# Regulators3.net
KiCad netlist of a schematic drawn in Altium Designer
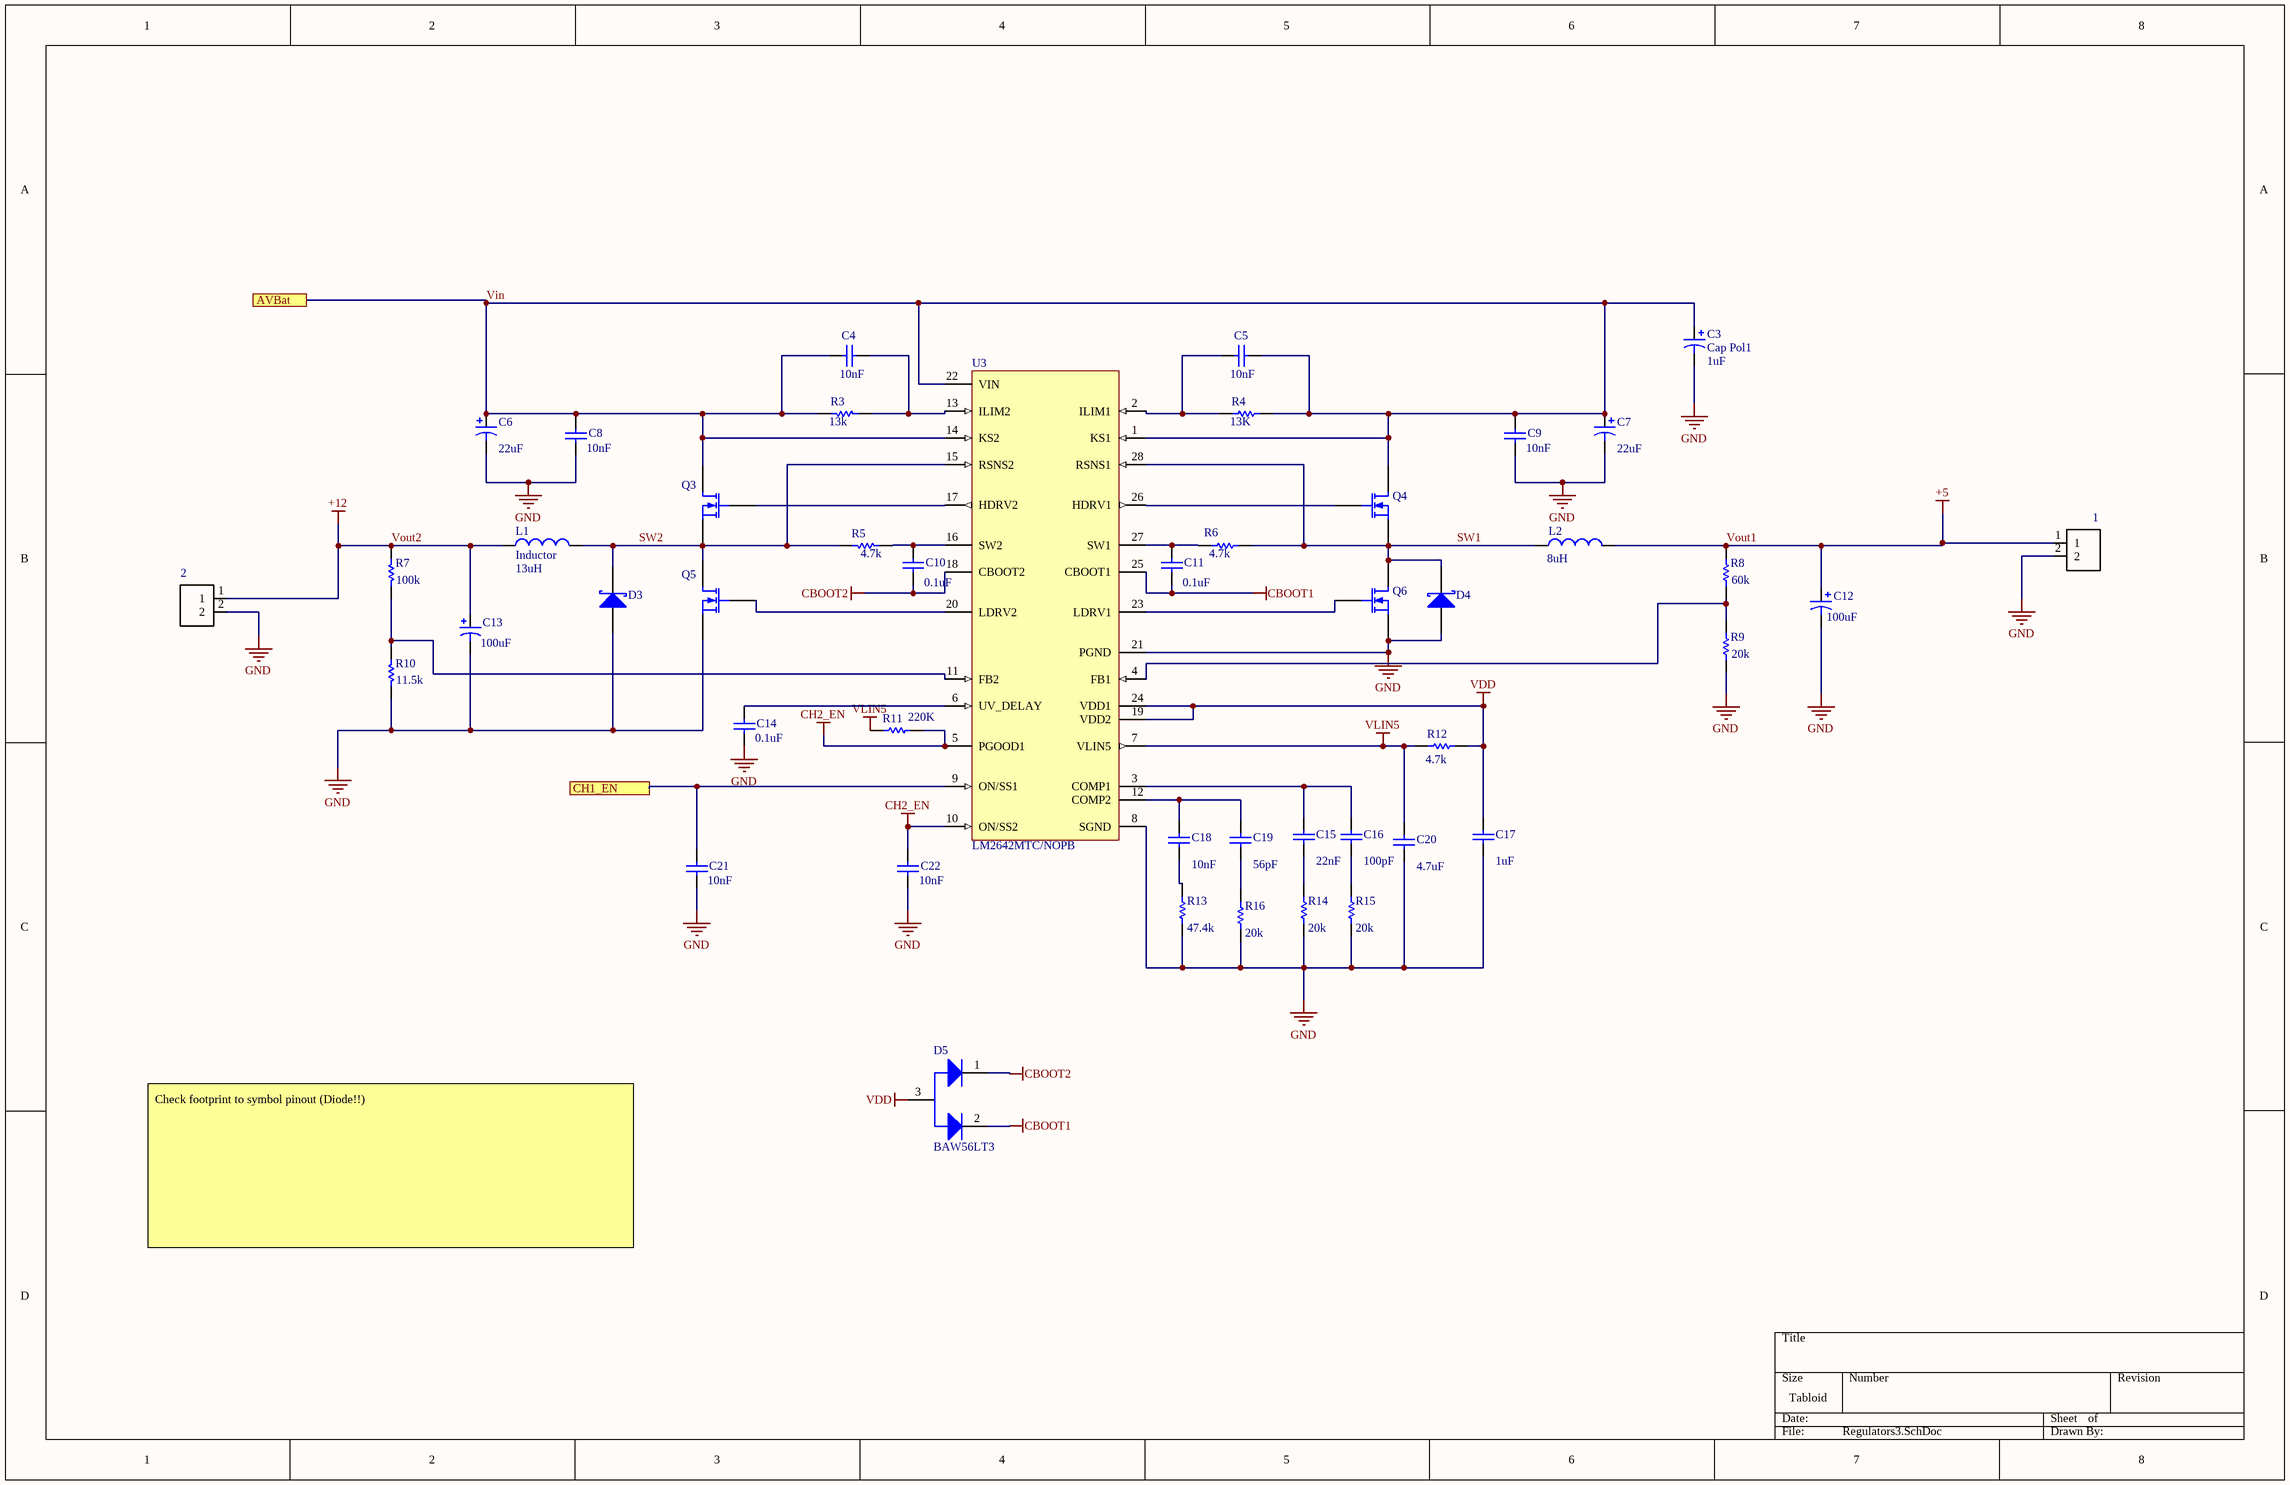
[diagram p0: Regulators3.SchDoc]

(export (version "E")
  (design (tool "Eeschema 10.0.6"))
  (components
    (comp (ref "1")
      (value "282836-2")
      (footprint "*CONN_282836-2")
      (description "Connector, Terminal Block; Wire Receptacle; 2 Pos.; 16-30 AWG; 0.197 in. CL; Sid")
      (fields (field (name "DIGI-KEY_PART_NUMBER") "A98076-ND") (field (name "MF") "TE Connectivity"))
      (libsource (lib "TerminalBlockx2") (part "282836-2"))
    )
    (comp (ref "2")
      (value "282836-2")
      (footprint "*CONN_282836-2")
      (description "Connector, Terminal Block; Wire Receptacle; 2 Pos.; 16-30 AWG; 0.197 in. CL; Sid")
      (fields (field (name "DIGI-KEY_PART_NUMBER") "A98076-ND") (field (name "MF") "TE Connectivity"))
      (libsource (lib "TerminalBlockx2") (part "282836-2"))
    )
    (comp (ref "C3")
      (value "Cap Pol1")
      (footprint "1u50VcapE")
      (description "Polarized Capacitor (Radial)")
      (fields (field (name "ALTIUM_VALUE") "1uF") (field (name "PUBLISHER") "Altium Limited"))
      (libsource (lib "Miscellaneous Devices") (part "Cap Pol1"))
    )
    (comp (ref "C4")
      (value "10nF")
      (footprint "1608[0603]")
      (description "Capacitor")
      (fields (field (name "Comment") "Cap") (field (name "PUBLISHER") "Altium Limited"))
      (libsource (lib "Miscellaneous Devices") (part "Cap"))
    )
    (comp (ref "C5")
      (value "10nF")
      (footprint "1608[0603]")
      (description "Capacitor")
      (fields (field (name "Comment") "Cap") (field (name "PUBLISHER") "Altium Limited"))
      (libsource (lib "Miscellaneous Devices") (part "Cap"))
    )
    (comp (ref "C6")
      (value "22uF")
      (footprint "22u16VcapE")
      (description "Polarized Capacitor (Radial)")
      (fields (field (name "Comment") "Cap Pol1") (field (name "PUBLISHER") "Altium Limited"))
      (libsource (lib "") (part "Cap Pol1_1"))
    )
    (comp (ref "C7")
      (value "22uF")
      (footprint "22u16VcapE")
      (description "Polarized Capacitor (Radial)")
      (fields (field (name "Comment") "Cap Pol1") (field (name "PUBLISHER") "Altium Limited"))
      (libsource (lib "Miscellaneous Devices") (part "Cap Pol1"))
    )
    (comp (ref "C8")
      (value "10nF")
      (footprint "1608[0603]")
      (description "Capacitor")
      (fields (field (name "Comment") "Cap") (field (name "PUBLISHER") "Altium Limited"))
      (libsource (lib "Miscellaneous Devices") (part "Cap"))
    )
    (comp (ref "C9")
      (value "10nF")
      (footprint "1608[0603]")
      (description "Capacitor")
      (fields (field (name "Comment") "Cap") (field (name "PUBLISHER") "Altium Limited"))
      (libsource (lib "Miscellaneous Devices") (part "Cap"))
    )
    (comp (ref "C10")
      (value "0.1uF")
      (footprint "1608[0603]")
      (description "Capacitor")
      (fields (field (name "Comment") "Cap") (field (name "PUBLISHER") "Altium Limited"))
      (libsource (lib "Miscellaneous Devices") (part "Cap"))
    )
    (comp (ref "C11")
      (value "0.1uF")
      (footprint "1608[0603]")
      (description "Capacitor")
      (fields (field (name "Comment") "Cap") (field (name "PUBLISHER") "Altium Limited"))
      (libsource (lib "Miscellaneous Devices") (part "Cap"))
    )
    (comp (ref "C12")
      (value "100uF")
      (footprint "*CAPAE660X800N")
      (description "Polarized Capacitor (Radial)")
      (fields (field (name "Comment") "Cap Pol1") (field (name "PUBLISHER") "Altium Limited"))
      (libsource (lib "Miscellaneous Devices") (part "Cap Pol1"))
    )
    (comp (ref "C13")
      (value "100uF")
      (footprint "*CAPAE660X800N")
      (description "Polarized Capacitor (Radial)")
      (fields (field (name "Comment") "Cap Pol1") (field (name "PUBLISHER") "Altium Limited"))
      (libsource (lib "") (part "Cap Pol1_1"))
    )
    (comp (ref "C14")
      (value "0.1uF")
      (footprint "1608[0603]")
      (description "Capacitor")
      (fields (field (name "Comment") "Cap") (field (name "PUBLISHER") "Altium Limited"))
      (libsource (lib "Miscellaneous Devices") (part "Cap"))
    )
    (comp (ref "C15")
      (value "22nF")
      (footprint "1608[0603]")
      (description "Capacitor")
      (fields (field (name "Comment") "Cap") (field (name "PUBLISHER") "Altium Limited"))
      (libsource (lib "Miscellaneous Devices") (part "Cap"))
    )
    (comp (ref "C16")
      (value "100pF")
      (footprint "1608[0603]")
      (description "Capacitor")
      (fields (field (name "Comment") "Cap") (field (name "PUBLISHER") "Altium Limited"))
      (libsource (lib "Miscellaneous Devices") (part "Cap"))
    )
    (comp (ref "C17")
      (value "1uF")
      (footprint "1608[0603]")
      (description "Capacitor")
      (fields (field (name "Comment") "Cap") (field (name "PUBLISHER") "Altium Limited"))
      (libsource (lib "Miscellaneous Devices") (part "Cap"))
    )
    (comp (ref "C18")
      (value "10nF")
      (footprint "1608[0603]")
      (description "Capacitor")
      (fields (field (name "Comment") "Cap") (field (name "PUBLISHER") "Altium Limited"))
      (libsource (lib "Miscellaneous Devices") (part "Cap"))
    )
    (comp (ref "C19")
      (value "56pF")
      (footprint "1608[0603]")
      (description "Capacitor")
      (fields (field (name "Comment") "Cap") (field (name "PUBLISHER") "Altium Limited"))
      (libsource (lib "Miscellaneous Devices") (part "Cap"))
    )
    (comp (ref "C20")
      (value "4.7uF")
      (footprint "1608[0603]")
      (description "Capacitor")
      (fields (field (name "Comment") "Cap") (field (name "PUBLISHER") "Altium Limited"))
      (libsource (lib "Miscellaneous Devices") (part "Cap"))
    )
    (comp (ref "C21")
      (value "10nF")
      (footprint "1608[0603]")
      (description "Capacitor")
      (fields (field (name "Comment") "Cap") (field (name "PUBLISHER") "Altium Limited"))
      (libsource (lib "Miscellaneous Devices") (part "Cap"))
    )
    (comp (ref "C22")
      (value "10nF")
      (footprint "1608[0603]")
      (description "Capacitor")
      (fields (field (name "Comment") "Cap") (field (name "PUBLISHER") "Altium Limited"))
      (libsource (lib "Miscellaneous Devices") (part "Cap"))
    )
    (comp (ref "D3")
      (value "Diode MBRS140t3")
      (footprint "*DIOM5227X270N_S1M(Primary)")
      (description "Schottky Rectifier")
      (fields (field (name "PUBLISHER") "Altium Limited"))
      (libsource (lib "Miscellaneous Devices") (part "Diode 18TQ045"))
    )
    (comp (ref "D4")
      (value "Diode MBRS140t3")
      (footprint "*DIOM5227X270N_S1M(Primary)")
      (description "Schottky Rectifier")
      (fields (field (name "PUBLISHER") "Altium Limited"))
      (libsource (lib "Miscellaneous Devices") (part "Diode 18TQ045"))
    )
    (comp (ref "D5")
      (value "BAW56LT3")
      (footprint "ONSC-SOT-23-3-318-08_V")
      (description "Dual Switching Diodes, Common Anode, 3-Pin SOT-23, Tape and Reel")
      (fields (field (name "MANUFACTURER") "On Semiconductor"))
      (libsource (lib "ON Semi Small Signal Switching Diodes") (part "BAW56LT3"))
    )
    (comp (ref "L1")
      (value "Inductor")
      (footprint "Inductor")
      (fields (field (name "ALTIUM_VALUE") "13uH") (field (name "PUBLISHER") "Altium Limited"))
      (libsource (lib "Miscellaneous Devices") (part "Inductor"))
    )
    (comp (ref "L2")
      (value "8uH")
      (footprint "Inductor")
      (description "Inductor")
      (fields (field (name "PUBLISHER") "Altium Limited"))
      (libsource (lib "Miscellaneous Devices") (part "Inductor"))
    )
    (comp (ref "Q3")
      (value "MOSFET-N")
      (footprint "SO8_L")
      (description "N-Channel MOSFET")
      (fields (field (name "PUBLISHER") "Altium Limited"))
      (libsource (lib "Miscellaneous Devices") (part "MOSFET-N"))
    )
    (comp (ref "Q4")
      (value "MOSFET-N")
      (footprint "SO8_L")
      (description "N-Channel MOSFET")
      (fields (field (name "PUBLISHER") "Altium Limited"))
      (libsource (lib "Miscellaneous Devices") (part "MOSFET-N"))
    )
    (comp (ref "Q5")
      (value "MOSFET-N")
      (footprint "SO8_L")
      (description "N-Channel MOSFET")
      (fields (field (name "PUBLISHER") "Altium Limited"))
      (libsource (lib "Miscellaneous Devices") (part "MOSFET-N"))
    )
    (comp (ref "Q6")
      (value "MOSFET-N")
      (footprint "SO8_L")
      (description "N-Channel MOSFET")
      (fields (field (name "PUBLISHER") "Altium Limited"))
      (libsource (lib "Miscellaneous Devices") (part "MOSFET-N"))
    )
    (comp (ref "R3")
      (value "13k")
      (footprint "1608[0603]")
      (description "Resistor")
      (fields (field (name "Comment") "Res1") (field (name "PUBLISHER") "Altium Limited"))
      (libsource (lib "Miscellaneous Devices") (part "Res1"))
    )
    (comp (ref "R4")
      (value "13K")
      (footprint "1608[0603]")
      (description "Resistor")
      (fields (field (name "Comment") "Res1") (field (name "PUBLISHER") "Altium Limited"))
      (libsource (lib "Miscellaneous Devices") (part "Res1"))
    )
    (comp (ref "R5")
      (value "4.7k")
      (footprint "1608[0603]")
      (description "Resistor")
      (fields (field (name "Comment") "Res1") (field (name "PUBLISHER") "Altium Limited"))
      (libsource (lib "Miscellaneous Devices") (part "Res1"))
    )
    (comp (ref "R6")
      (value "4.7k")
      (footprint "1608[0603]")
      (description "Resistor")
      (fields (field (name "Comment") "Res1") (field (name "PUBLISHER") "Altium Limited"))
      (libsource (lib "Miscellaneous Devices") (part "Res1"))
    )
    (comp (ref "R7")
      (value "100k")
      (footprint "1608[0603]")
      (description "Resistor")
      (fields (field (name "Comment") "Res1") (field (name "PUBLISHER") "Altium Limited"))
      (libsource (lib "Miscellaneous Devices") (part "Res1"))
    )
    (comp (ref "R8")
      (value "60k")
      (footprint "1608[0603]")
      (description "Resistor")
      (fields (field (name "Comment") "Res1") (field (name "PUBLISHER") "Altium Limited"))
      (libsource (lib "Miscellaneous Devices") (part "Res1"))
    )
    (comp (ref "R9")
      (value "20k")
      (footprint "1608[0603]")
      (description "Resistor")
      (fields (field (name "Comment") "Res1") (field (name "PUBLISHER") "Altium Limited"))
      (libsource (lib "Miscellaneous Devices") (part "Res1"))
    )
    (comp (ref "R10")
      (value "11.5k")
      (footprint "1608[0603]")
      (description "Resistor")
      (fields (field (name "Comment") "Res1") (field (name "PUBLISHER") "Altium Limited"))
      (libsource (lib "Miscellaneous Devices") (part "Res1"))
    )
    (comp (ref "R11")
      (value "220K")
      (footprint "1608[0603]")
      (description "Resistor")
      (fields (field (name "Comment") "Res1") (field (name "PUBLISHER") "Altium Limited"))
      (libsource (lib "Miscellaneous Devices") (part "Res1"))
    )
    (comp (ref "R12")
      (value "4.7k")
      (footprint "1608[0603]")
      (description "Resistor")
      (fields (field (name "Comment") "Res1") (field (name "PUBLISHER") "Altium Limited"))
      (libsource (lib "Miscellaneous Devices") (part "Res1"))
    )
    (comp (ref "R13")
      (value "47.4k")
      (footprint "1608[0603]")
      (description "Resistor")
      (fields (field (name "Comment") "Res1") (field (name "PUBLISHER") "Altium Limited"))
      (libsource (lib "Miscellaneous Devices") (part "Res1"))
    )
    (comp (ref "R14")
      (value "20k")
      (footprint "1608[0603]")
      (description "Resistor")
      (fields (field (name "Comment") "Res1") (field (name "PUBLISHER") "Altium Limited"))
      (libsource (lib "Miscellaneous Devices") (part "Res1"))
    )
    (comp (ref "R15")
      (value "20k")
      (footprint "1608[0603]")
      (description "Resistor")
      (fields (field (name "Comment") "Res1") (field (name "PUBLISHER") "Altium Limited"))
      (libsource (lib "Miscellaneous Devices") (part "Res1"))
    )
    (comp (ref "R16")
      (value "20k")
      (footprint "1608[0603]")
      (description "Resistor")
      (fields (field (name "Comment") "Res1") (field (name "PUBLISHER") "Altium Limited"))
      (libsource (lib "Miscellaneous Devices") (part "Res1"))
    )
    (comp (ref "U3")
      (value "LM2642MTC/NOPB")
      (footprint "MTC28_N")
      (description "Two-Phase Synchronous Step-Down Switching Controller, 28-pin TSSOP, Pb-Free")
      (fields (field (name "MANUFACTURER") "National Semiconductor"))
      (libsource (lib "National Semiconductor Switcher") (part "LM2642MTC/NOPB"))
    )
  )
  (nets
    (net (code "1") (name "+5") (class "Default")
      (node (ref "1") (pin "1") (pinfunction "1_1") (pintype "passive"))
      (node (ref "C12") (pin "1") (pinfunction "1_1") (pintype "passive"))
      (node (ref "L2") (pin "2") (pinfunction "2_2") (pintype "passive"))
      (node (ref "R8") (pin "2") (pinfunction "2_2") (pintype "passive"))
    )
    (net (code "2") (name "+12") (class "Default")
      (node (ref "2") (pin "1") (pinfunction "1_1") (pintype "passive"))
      (node (ref "C13") (pin "1") (pinfunction "1_1") (pintype "passive"))
      (node (ref "L1") (pin "1") (pinfunction "1_1") (pintype "passive"))
      (node (ref "R7") (pin "2") (pinfunction "2_2") (pintype "passive"))
    )
    (net (code "3") (name "/CH1_EN") (class "Default")
      (node (ref "C21") (pin "2") (pinfunction "2_2") (pintype "passive"))
      (node (ref "U3") (pin "9") (pinfunction "ON/SS1_9") (pintype "input"))
    )
    (net (code "4") (name "/SW1") (class "Default")
      (node (ref "D4") (pin "1") (pinfunction "K_1") (pintype "passive"))
      (node (ref "L2") (pin "1") (pinfunction "1_1") (pintype "passive"))
      (node (ref "Q4") (pin "3") (pinfunction "S_3") (pintype "passive"))
      (node (ref "Q6") (pin "1") (pinfunction "D_1") (pintype "passive"))
      (node (ref "R6") (pin "2") (pinfunction "2_2") (pintype "passive"))
      (node (ref "U3") (pin "28") (pinfunction "RSNS1_28") (pintype "input"))
    )
    (net (code "5") (name "/SW2") (class "Default")
      (node (ref "D3") (pin "1") (pinfunction "K_1") (pintype "passive"))
      (node (ref "L1") (pin "2") (pinfunction "2_2") (pintype "passive"))
      (node (ref "Q3") (pin "3") (pinfunction "S_3") (pintype "passive"))
      (node (ref "Q5") (pin "1") (pinfunction "D_1") (pintype "passive"))
      (node (ref "R5") (pin "2") (pinfunction "2_2") (pintype "passive"))
      (node (ref "U3") (pin "15") (pinfunction "RSNS2_15") (pintype "input"))
    )
    (net (code "6") (name "/Vin") (class "Default")
      (node (ref "C3") (pin "1") (pinfunction "1_1") (pintype "passive"))
      (node (ref "C4") (pin "2") (pinfunction "2_2") (pintype "passive"))
      (node (ref "C5") (pin "2") (pinfunction "2_2") (pintype "passive"))
      (node (ref "C6") (pin "1") (pinfunction "1_1") (pintype "passive"))
      (node (ref "C7") (pin "1") (pinfunction "1_1") (pintype "passive"))
      (node (ref "C8") (pin "2") (pinfunction "2_2") (pintype "passive"))
      (node (ref "C9") (pin "2") (pinfunction "2_2") (pintype "passive"))
      (node (ref "Q3") (pin "1") (pinfunction "D_1") (pintype "passive"))
      (node (ref "Q4") (pin "1") (pinfunction "D_1") (pintype "passive"))
      (node (ref "R3") (pin "2") (pinfunction "2_2") (pintype "passive"))
      (node (ref "R4") (pin "2") (pinfunction "2_2") (pintype "passive"))
      (node (ref "U3") (pin "1") (pinfunction "KS1_1") (pintype "input"))
      (node (ref "U3") (pin "14") (pinfunction "KS2_14") (pintype "input"))
      (node (ref "U3") (pin "22") (pinfunction "VIN_22") (pintype "power_in"))
    )
    (net (code "7") (name "CBOOT1") (class "Default")
      (node (ref "C11") (pin "1") (pinfunction "1_1") (pintype "passive"))
      (node (ref "D5") (pin "2") (pinfunction "K2_2") (pintype "passive"))
      (node (ref "U3") (pin "25") (pinfunction "CBOOT1_25") (pintype "passive"))
    )
    (net (code "8") (name "CBOOT2") (class "Default")
      (node (ref "C10") (pin "1") (pinfunction "1_1") (pintype "passive"))
      (node (ref "D5") (pin "1") (pinfunction "K1_1") (pintype "passive"))
      (node (ref "U3") (pin "18") (pinfunction "CBOOT2_18") (pintype "passive"))
    )
    (net (code "9") (name "CH2_EN") (class "Default")
      (node (ref "C22") (pin "2") (pinfunction "2_2") (pintype "passive"))
      (node (ref "R11") (pin "2") (pinfunction "2_2") (pintype "passive"))
      (node (ref "U3") (pin "10") (pinfunction "ON/SS2_10") (pintype "input"))
      (node (ref "U3") (pin "5") (pinfunction "PGOOD1_5") (pintype "open_collector"))
    )
    (net (code "10") (name "GND") (class "Default")
      (node (ref "1") (pin "2") (pinfunction "2_2") (pintype "passive"))
      (node (ref "2") (pin "2") (pinfunction "2_2") (pintype "passive"))
      (node (ref "C12") (pin "2") (pinfunction "2_2") (pintype "passive"))
      (node (ref "C13") (pin "2") (pinfunction "2_2") (pintype "passive"))
      (node (ref "C14") (pin "1") (pinfunction "1_1") (pintype "passive"))
      (node (ref "C17") (pin "1") (pinfunction "1_1") (pintype "passive"))
      (node (ref "C20") (pin "1") (pinfunction "1_1") (pintype "passive"))
      (node (ref "C21") (pin "1") (pinfunction "1_1") (pintype "passive"))
      (node (ref "C22") (pin "1") (pinfunction "1_1") (pintype "passive"))
      (node (ref "C3") (pin "2") (pinfunction "2_2") (pintype "passive"))
      (node (ref "C6") (pin "2") (pinfunction "2_2") (pintype "passive"))
      (node (ref "C7") (pin "2") (pinfunction "2_2") (pintype "passive"))
      (node (ref "C8") (pin "1") (pinfunction "1_1") (pintype "passive"))
      (node (ref "C9") (pin "1") (pinfunction "1_1") (pintype "passive"))
      (node (ref "D3") (pin "3") (pinfunction "A_3") (pintype "passive"))
      (node (ref "D4") (pin "3") (pinfunction "A_3") (pintype "passive"))
      (node (ref "Q5") (pin "3") (pinfunction "S_3") (pintype "passive"))
      (node (ref "Q6") (pin "3") (pinfunction "S_3") (pintype "passive"))
      (node (ref "R10") (pin "1") (pinfunction "1_1") (pintype "passive"))
      (node (ref "R13") (pin "1") (pinfunction "1_1") (pintype "passive"))
      (node (ref "R14") (pin "1") (pinfunction "1_1") (pintype "passive"))
      (node (ref "R15") (pin "1") (pinfunction "1_1") (pintype "passive"))
      (node (ref "R16") (pin "1") (pinfunction "1_1") (pintype "passive"))
      (node (ref "R9") (pin "1") (pinfunction "1_1") (pintype "passive"))
      (node (ref "U3") (pin "21") (pinfunction "PGND_21") (pintype "power_in"))
      (node (ref "U3") (pin "8") (pinfunction "SGND_8") (pintype "power_in"))
    )
    (net (code "11") (name "Net-(C15-Pad1)") (class "Default")
      (node (ref "C15") (pin "1") (pinfunction "1_1") (pintype "passive"))
      (node (ref "R14") (pin "2") (pinfunction "2_2") (pintype "passive"))
    )
    (net (code "12") (name "Net-(C16-Pad1)") (class "Default")
      (node (ref "C16") (pin "1") (pinfunction "1_1") (pintype "passive"))
      (node (ref "R15") (pin "2") (pinfunction "2_2") (pintype "passive"))
    )
    (net (code "13") (name "Net-(C18-Pad1)") (class "Default")
      (node (ref "C18") (pin "1") (pinfunction "1_1") (pintype "passive"))
      (node (ref "R13") (pin "2") (pinfunction "2_2") (pintype "passive"))
    )
    (net (code "14") (name "Net-(C19-Pad1)") (class "Default")
      (node (ref "C19") (pin "1") (pinfunction "1_1") (pintype "passive"))
      (node (ref "R16") (pin "2") (pinfunction "2_2") (pintype "passive"))
    )
    (net (code "15") (name "Net-(Q3-G)") (class "Default")
      (node (ref "Q3") (pin "2") (pinfunction "G_2") (pintype "passive"))
      (node (ref "U3") (pin "17") (pinfunction "HDRV2_17") (pintype "output"))
    )
    (net (code "16") (name "Net-(Q4-G)") (class "Default")
      (node (ref "Q4") (pin "2") (pinfunction "G_2") (pintype "passive"))
      (node (ref "U3") (pin "26") (pinfunction "HDRV1_26") (pintype "output"))
    )
    (net (code "17") (name "Net-(Q5-G)") (class "Default")
      (node (ref "Q5") (pin "2") (pinfunction "G_2") (pintype "passive"))
      (node (ref "U3") (pin "20") (pinfunction "LDRV2_20") (pintype "power_in"))
    )
    (net (code "18") (name "Net-(Q6-G)") (class "Default")
      (node (ref "Q6") (pin "2") (pinfunction "G_2") (pintype "passive"))
      (node (ref "U3") (pin "23") (pinfunction "LDRV1_23") (pintype "power_in"))
    )
    (net (code "19") (name "Net-(U3-COMP1)") (class "Default")
      (node (ref "C15") (pin "2") (pinfunction "2_2") (pintype "passive"))
      (node (ref "C16") (pin "2") (pinfunction "2_2") (pintype "passive"))
      (node (ref "U3") (pin "3") (pinfunction "COMP1_3") (pintype "passive"))
    )
    (net (code "20") (name "Net-(U3-COMP2)") (class "Default")
      (node (ref "C18") (pin "2") (pinfunction "2_2") (pintype "passive"))
      (node (ref "C19") (pin "2") (pinfunction "2_2") (pintype "passive"))
      (node (ref "U3") (pin "12") (pinfunction "COMP2_12") (pintype "passive"))
    )
    (net (code "21") (name "Net-(U3-FB1)") (class "Default")
      (node (ref "R8") (pin "1") (pinfunction "1_1") (pintype "passive"))
      (node (ref "R9") (pin "2") (pinfunction "2_2") (pintype "passive"))
      (node (ref "U3") (pin "4") (pinfunction "FB1_4") (pintype "input"))
    )
    (net (code "22") (name "Net-(U3-FB2)") (class "Default")
      (node (ref "R10") (pin "2") (pinfunction "2_2") (pintype "passive"))
      (node (ref "R7") (pin "1") (pinfunction "1_1") (pintype "passive"))
      (node (ref "U3") (pin "11") (pinfunction "FB2_11") (pintype "input"))
    )
    (net (code "23") (name "Net-(U3-ILIM1)") (class "Default")
      (node (ref "C5") (pin "1") (pinfunction "1_1") (pintype "passive"))
      (node (ref "R4") (pin "1") (pinfunction "1_1") (pintype "passive"))
      (node (ref "U3") (pin "2") (pinfunction "ILIM1_2") (pintype "input"))
    )
    (net (code "24") (name "Net-(U3-ILIM2)") (class "Default")
      (node (ref "C4") (pin "1") (pinfunction "1_1") (pintype "passive"))
      (node (ref "R3") (pin "1") (pinfunction "1_1") (pintype "passive"))
      (node (ref "U3") (pin "13") (pinfunction "ILIM2_13") (pintype "input"))
    )
    (net (code "25") (name "Net-(U3-SW1)") (class "Default")
      (node (ref "C11") (pin "2") (pinfunction "2_2") (pintype "passive"))
      (node (ref "R6") (pin "1") (pinfunction "1_1") (pintype "passive"))
      (node (ref "U3") (pin "27") (pinfunction "SW1_27") (pintype "power_in"))
    )
    (net (code "26") (name "Net-(U3-SW2)") (class "Default")
      (node (ref "C10") (pin "2") (pinfunction "2_2") (pintype "passive"))
      (node (ref "R5") (pin "1") (pinfunction "1_1") (pintype "passive"))
      (node (ref "U3") (pin "16") (pinfunction "SW2_16") (pintype "power_in"))
    )
    (net (code "27") (name "Net-(U3-UV_DELAY)") (class "Default")
      (node (ref "C14") (pin "2") (pinfunction "2_2") (pintype "passive"))
      (node (ref "U3") (pin "6") (pinfunction "UV_DELAY_6") (pintype "input"))
    )
    (net (code "28") (name "VDD") (class "Default")
      (node (ref "C17") (pin "2") (pinfunction "2_2") (pintype "passive"))
      (node (ref "D5") (pin "3") (pinfunction "A_3") (pintype "passive"))
      (node (ref "R12") (pin "2") (pinfunction "2_2") (pintype "passive"))
      (node (ref "U3") (pin "19") (pinfunction "VDD2_19") (pintype "power_in"))
      (node (ref "U3") (pin "24") (pinfunction "VDD1_24") (pintype "power_in"))
    )
    (net (code "29") (name "VLIN5") (class "Default")
      (node (ref "C20") (pin "2") (pinfunction "2_2") (pintype "passive"))
      (node (ref "R11") (pin "1") (pinfunction "1_1") (pintype "passive"))
      (node (ref "R12") (pin "1") (pinfunction "1_1") (pintype "passive"))
      (node (ref "U3") (pin "7") (pinfunction "VLIN5_7") (pintype "output"))
    )
  )
)
